# Auxilary.net
KiCad netlist of a schematic drawn in Altium Designer
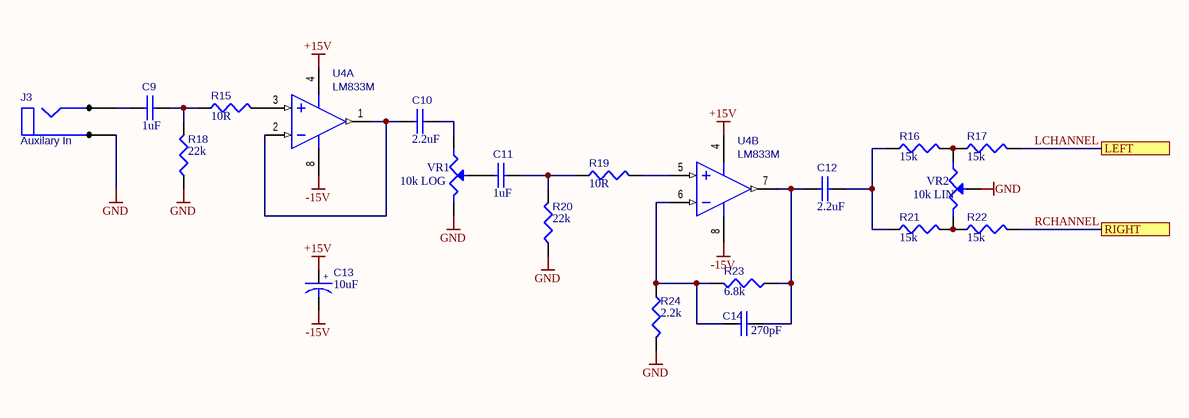
[diagram p0: Auxilary.SchDoc]

(export (version "E")
  (design (tool "Eeschema 10.0.6"))
  (components
    (comp (ref "C9")
      (value "1uF")
      (footprint "RB.2/.4-NP")
      (description "Capacitor")
      (libsource (lib "*") (part "CAP"))
    )
    (comp (ref "C10")
      (value "2.2uF")
      (footprint "RB.2/.4-NP")
      (description "Capacitor")
      (libsource (lib "*") (part "CAP"))
    )
    (comp (ref "C11")
      (value "1uF")
      (footprint "RB.2/.4-NP")
      (description "Capacitor")
      (libsource (lib "*") (part "CAP"))
    )
    (comp (ref "C12")
      (value "2.2uF")
      (footprint "RB.2/.4-NP")
      (description "Capacitor")
      (libsource (lib "*") (part "CAP"))
    )
    (comp (ref "C13")
      (value "10uF")
      (footprint "RB.2/.4")
      (description "Bi-Polar Capacitor")
      (libsource (lib "*") (part "CAPACITOR POL"))
    )
    (comp (ref "C14")
      (value "270pF")
      (footprint "RAD0.2")
      (description "Capacitor")
      (libsource (lib "*") (part "CAP"))
    )
    (comp (ref "J3")
      (value "Auxilary In")
      (footprint "JACK-6.25MM")
      (libsource (lib "*") (part "PHONEJACK MONO"))
    )
    (comp (ref "R15")
      (value "10R")
      (footprint "AXIAL0.4")
      (description "Resistor")
      (libsource (lib "") (part "RES1_2"))
    )
    (comp (ref "R16")
      (value "15k")
      (footprint "AXIAL0.4")
      (description "Resistor")
      (libsource (lib "") (part "RES1_2"))
    )
    (comp (ref "R17")
      (value "15k")
      (footprint "AXIAL0.4")
      (description "Resistor")
      (libsource (lib "") (part "RES1_2"))
    )
    (comp (ref "R18")
      (value "22k")
      (footprint "AXIAL0.4")
      (description "Resistor")
      (libsource (lib "") (part "RES1_3"))
    )
    (comp (ref "R19")
      (value "10R")
      (footprint "AXIAL0.4")
      (description "Resistor")
      (libsource (lib "") (part "RES1_2"))
    )
    (comp (ref "R20")
      (value "22k")
      (footprint "AXIAL0.4")
      (description "Resistor")
      (libsource (lib "") (part "RES1_3"))
    )
    (comp (ref "R21")
      (value "15k")
      (footprint "AXIAL0.4")
      (description "Resistor")
      (libsource (lib "") (part "RES1_2"))
    )
    (comp (ref "R22")
      (value "15k")
      (footprint "AXIAL0.4")
      (description "Resistor")
      (libsource (lib "") (part "RES1_2"))
    )
    (comp (ref "R23")
      (value "6.8k")
      (footprint "AXIAL0.4")
      (description "Resistor")
      (libsource (lib "") (part "RES1_1"))
    )
    (comp (ref "R24")
      (value "2.2k")
      (footprint "AXIAL0.4")
      (description "Resistor")
      (libsource (lib "*") (part "RES1"))
    )
    (comp (ref "U4")
      (value "LM833M")
      (footprint "DIP8")
      (description "Fast Settling Dual Operational Amplifier")
      (libsource (lib "*") (part "LM833M"))
    )
    (comp (ref "VR1")
      (value "10k LOG")
      (footprint "POT - 24MM")
      (description "Potentiometer")
      (libsource (lib "*") (part "POT1"))
    )
    (comp (ref "VR2")
      (value "10k LIN")
      (footprint "POT - 24MM")
      (description "Potentiometer")
      (libsource (lib "*") (part "POT1"))
    )
  )
  (nets
    (net (code "1") (name "+15V") (class "Default")
      (node (ref "C13") (pin "1") (pinfunction "1_1") (pintype "passive"))
      (node (ref "U4") (pin "4") (pinfunction "V-_4") (pintype "power_in"))
    )
    (net (code "2") (name "-15V") (class "Default")
      (node (ref "C13") (pin "2") (pinfunction "2_2") (pintype "passive"))
      (node (ref "U4") (pin "8") (pinfunction "V+_8") (pintype "power_in"))
    )
    (net (code "3") (name "/LCHANNEL") (class "Default")
      (node (ref "R17") (pin "2") (pinfunction "2_2") (pintype "passive"))
    )
    (net (code "4") (name "/RCHANNEL") (class "Default")
      (node (ref "R22") (pin "2") (pinfunction "2_2") (pintype "passive"))
    )
    (net (code "5") (name "GND") (class "Default")
      (node (ref "J3") (pin "3") (pinfunction "C_3") (pintype "passive"))
      (node (ref "R18") (pin "1") (pinfunction "1_1") (pintype "passive"))
      (node (ref "R20") (pin "1") (pinfunction "1_1") (pintype "passive"))
      (node (ref "R24") (pin "2") (pinfunction "2_2") (pintype "passive"))
      (node (ref "VR1") (pin "3") (pinfunction "3_3") (pintype "passive"))
      (node (ref "VR2") (pin "2") (pinfunction "W_2") (pintype "passive"))
    )
    (net (code "6") (name "Net-(C9-Pad2)") (class "Default")
      (node (ref "C9") (pin "2") (pinfunction "2_2") (pintype "passive"))
      (node (ref "R15") (pin "1") (pinfunction "1_1") (pintype "passive"))
      (node (ref "R18") (pin "2") (pinfunction "2_2") (pintype "passive"))
    )
    (net (code "7") (name "Net-(C10-Pad2)") (class "Default")
      (node (ref "C10") (pin "2") (pinfunction "2_2") (pintype "passive"))
      (node (ref "VR1") (pin "1") (pinfunction "1_1") (pintype "passive"))
    )
    (net (code "8") (name "Net-(C11-Pad2)") (class "Default")
      (node (ref "C11") (pin "2") (pinfunction "2_2") (pintype "passive"))
      (node (ref "R19") (pin "1") (pinfunction "1_1") (pintype "passive"))
      (node (ref "R20") (pin "2") (pinfunction "2_2") (pintype "passive"))
    )
    (net (code "9") (name "Net-(C12-Pad2)") (class "Default")
      (node (ref "C12") (pin "2") (pinfunction "2_2") (pintype "passive"))
      (node (ref "R16") (pin "1") (pinfunction "1_1") (pintype "passive"))
      (node (ref "R21") (pin "1") (pinfunction "1_1") (pintype "passive"))
    )
    (net (code "10") (name "Net-(J3-A)") (class "Default")
      (node (ref "C9") (pin "1") (pinfunction "1_1") (pintype "passive"))
      (node (ref "J3") (pin "1") (pinfunction "A_1") (pintype "passive"))
    )
    (net (code "11") (name "Net-(R16-Pad2)") (class "Default")
      (node (ref "R16") (pin "2") (pinfunction "2_2") (pintype "passive"))
      (node (ref "R17") (pin "1") (pinfunction "1_1") (pintype "passive"))
      (node (ref "VR2") (pin "1") (pinfunction "1_1") (pintype "passive"))
    )
    (net (code "12") (name "Net-(R21-Pad2)") (class "Default")
      (node (ref "R21") (pin "2") (pinfunction "2_2") (pintype "passive"))
      (node (ref "R22") (pin "1") (pinfunction "1_1") (pintype "passive"))
      (node (ref "VR2") (pin "3") (pinfunction "3_3") (pintype "passive"))
    )
    (net (code "13") (name "Net-(U4A-IN1+)") (class "Default")
      (node (ref "R15") (pin "2") (pinfunction "2_2") (pintype "passive"))
      (node (ref "U4") (pin "3") (pinfunction "IN1+_3") (pintype "input"))
    )
    (net (code "14") (name "Net-(U4A-IN1-)") (class "Default")
      (node (ref "C10") (pin "1") (pinfunction "1_1") (pintype "passive"))
      (node (ref "U4") (pin "1") (pinfunction "OUT1_1") (pintype "output"))
      (node (ref "U4") (pin "2") (pinfunction "IN1-_2") (pintype "input"))
    )
    (net (code "15") (name "Net-(U4B-IN2+)") (class "Default")
      (node (ref "R19") (pin "2") (pinfunction "2_2") (pintype "passive"))
      (node (ref "U4") (pin "5") (pinfunction "IN2+_5") (pintype "input"))
    )
    (net (code "16") (name "Net-(U4B-IN2-)") (class "Default")
      (node (ref "C14") (pin "1") (pinfunction "1_1") (pintype "passive"))
      (node (ref "R23") (pin "2") (pinfunction "2_2") (pintype "passive"))
      (node (ref "R24") (pin "1") (pinfunction "1_1") (pintype "passive"))
      (node (ref "U4") (pin "6") (pinfunction "IN2-_6") (pintype "input"))
    )
    (net (code "17") (name "Net-(U4B-OUT2)") (class "Default")
      (node (ref "C12") (pin "1") (pinfunction "1_1") (pintype "passive"))
      (node (ref "C14") (pin "2") (pinfunction "2_2") (pintype "passive"))
      (node (ref "R23") (pin "1") (pinfunction "1_1") (pintype "passive"))
      (node (ref "U4") (pin "7") (pinfunction "OUT2_7") (pintype "output"))
    )
    (net (code "18") (name "Net-(VR1-W)") (class "Default")
      (node (ref "C11") (pin "1") (pinfunction "1_1") (pintype "passive"))
      (node (ref "VR1") (pin "2") (pinfunction "W_2") (pintype "passive"))
    )
  )
)
